# USB.net
KiCad netlist of a schematic drawn in Altium Designer
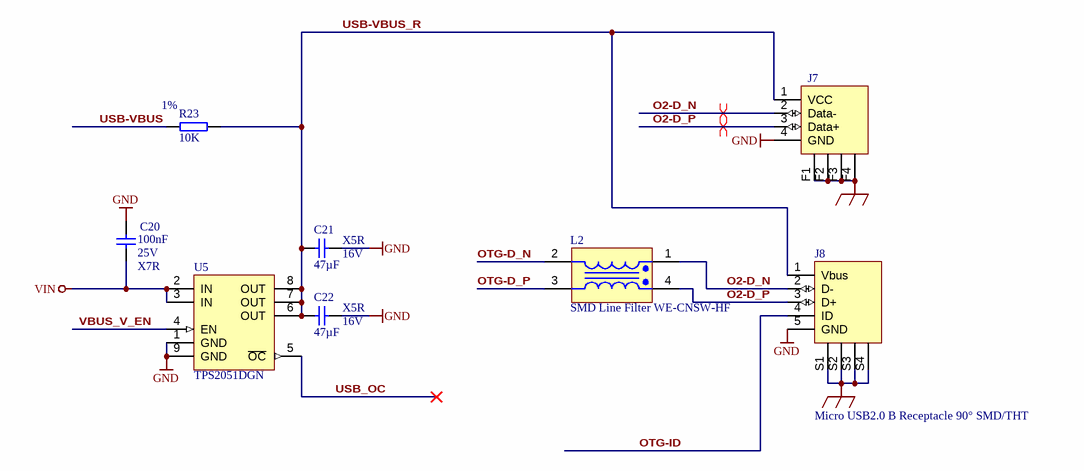
[diagram p0: USB.SchDoc]

(export (version "E")
  (design (tool "Eeschema 10.0.6"))
  (components
    (comp (ref "C20")
      (value "100nF")
      (footprint "CAPC1005X55N")
      (description "KON 100nF 25V X5R SMD")
      (fields (field (name "VOLTAGE") "25V") (field (name "TECHNOLOGY") "X7R"))
      (libsource (lib "TE") (part "CAP-NP"))
    )
    (comp (ref "C21")
      (value "47µF")
      (footprint "CAPC3216X180N")
      (description "KON 47µF 16V  X5R SMD 20%")
      (fields
        (field (name "VOLTAGE") "16V")
        (field (name "TECHNOLOGY") "X5R")
        (field (name "TOLERANCE") "20%")
      )
      (libsource (lib "TE") (part "CAP-NP"))
    )
    (comp (ref "C22")
      (value "47µF")
      (footprint "CAPC3216X180N")
      (description "KON 47µF 16V  X5R SMD 20%")
      (fields
        (field (name "VOLTAGE") "16V")
        (field (name "TECHNOLOGY") "X5R")
        (field (name "TOLERANCE") "20%")
      )
      (libsource (lib "TE") (part "CAP-NP"))
    )
    (comp (ref "J7")
      (value "USB A Buchse 90°")
      (footprint "73725-0110BLF")
      (libsource (lib "TE") (part "USB A 90"))
    )
    (comp (ref "J8")
      (value "Micro USB2.0 B Receptacle 90° SMD/THT")
      (footprint "629105150521")
      (fields (field (name "HELPURL") "‪B:\\AD\\adlib\\datasheet\\629105150521"))
      (libsource (lib "TE") (part "629105150521"))
    )
    (comp (ref "L2")
      (value "SMD Line Filter WE-CNSW-HF")
      (footprint "WE-CNSW-HF")
      (description "Stromkompensierter SMD Line Filter HF 320mA 0,24Ohm 50V")
      (fields (field (name "VOLTAGE") "320mA"))
      (libsource (lib "TE") (part "WE-CNSW-HF"))
    )
    (comp (ref "R23")
      (value "10K")
      (footprint "RESC1005X40N")
      (description "WID SMD 10K 1% 0,063W")
      (fields (field (name "TOLERANCE") "1%"))
      (libsource (lib "TE") (part "RES"))
    )
    (comp (ref "U5")
      (value "TPS2051DGN")
      (footprint "SOP65P488X107-9N-TI")
      (description "TPS2051BDGN")
      (libsource (lib "TE") (part "TPS2051DGN"))
    )
  )
  (nets
    (net (code "1") (name "/O2-D_N") (class "Default")
      (node (ref "J7") (pin "2") (pinfunction "Data-_2") (pintype "bidirectional"))
      (node (ref "J8") (pin "2") (pinfunction "D-_2") (pintype "bidirectional"))
      (node (ref "L2") (pin "1") (pintype "passive"))
    )
    (net (code "2") (name "/O2-D_P") (class "Default")
      (node (ref "J7") (pin "3") (pinfunction "Data+_3") (pintype "bidirectional"))
      (node (ref "J8") (pin "3") (pinfunction "D+_3") (pintype "bidirectional"))
      (node (ref "L2") (pin "4") (pintype "passive"))
    )
    (net (code "3") (name "/OTG-D_N") (class "Default") (node (ref "L2") (pin "2") (pintype "passive")))
    (net (code "4") (name "/OTG-D_P") (class "Default") (node (ref "L2") (pin "3") (pintype "passive")))
    (net (code "5") (name "/OTG-ID") (class "Default")
      (node (ref "J8") (pin "4") (pinfunction "ID_4") (pintype "passive"))
    )
    (net (code "6") (name "/USB-VBUS") (class "Default")
      (node (ref "R23") (pin "1") (pinfunction "1_1") (pintype "passive"))
    )
    (net (code "7") (name "/USB-VBUS_R") (class "Default")
      (node (ref "C21") (pin "1") (pinfunction "1_1") (pintype "passive"))
      (node (ref "C22") (pin "1") (pinfunction "1_1") (pintype "passive"))
      (node (ref "J7") (pin "1") (pinfunction "VCC_1") (pintype "power_in"))
      (node (ref "J8") (pin "1") (pinfunction "Vbus_1") (pintype "power_in"))
      (node (ref "R23") (pin "2") (pinfunction "2_2") (pintype "passive"))
      (node (ref "U5") (pin "6") (pinfunction "OUT_6") (pintype "power_in"))
      (node (ref "U5") (pin "7") (pinfunction "OUT_7") (pintype "power_in"))
      (node (ref "U5") (pin "8") (pinfunction "OUT_8") (pintype "power_in"))
    )
    (net (code "8") (name "/USB_OC") (class "Default")
      (node (ref "U5") (pin "5") (pinfunction "~{OC}_5") (pintype "output+no_connect"))
    )
    (net (code "9") (name "/VBUS_V_EN") (class "Default")
      (node (ref "U5") (pin "4") (pinfunction "EN_4") (pintype "input"))
    )
    (net (code "10") (name "FGND") (class "Default")
      (node (ref "J7") (pin "F1") (pinfunction "Frame_F1") (pintype "passive"))
      (node (ref "J7") (pin "F2") (pinfunction "Frame_F2") (pintype "passive"))
      (node (ref "J7") (pin "F3") (pinfunction "Frame_F3") (pintype "passive"))
      (node (ref "J7") (pin "F4") (pinfunction "Frame_F4") (pintype "passive"))
      (node (ref "J8") (pin "S1") (pinfunction "S1_S1") (pintype "passive"))
      (node (ref "J8") (pin "S2") (pinfunction "S2_S2") (pintype "passive"))
      (node (ref "J8") (pin "S3") (pinfunction "S3_S3") (pintype "passive"))
      (node (ref "J8") (pin "S4") (pinfunction "S4_S4") (pintype "passive"))
    )
    (net (code "11") (name "GND") (class "Default")
      (node (ref "C20") (pin "2") (pinfunction "2_2") (pintype "passive"))
      (node (ref "C21") (pin "2") (pinfunction "2_2") (pintype "passive"))
      (node (ref "C22") (pin "2") (pinfunction "2_2") (pintype "passive"))
      (node (ref "J7") (pin "4") (pinfunction "GND_4") (pintype "power_in"))
      (node (ref "J8") (pin "5") (pinfunction "GND_5") (pintype "power_in"))
      (node (ref "U5") (pin "1") (pinfunction "GND_1") (pintype "power_in"))
      (node (ref "U5") (pin "9") (pinfunction "GND_9") (pintype "power_in"))
    )
    (net (code "12") (name "VIN") (class "Default")
      (node (ref "C20") (pin "1") (pinfunction "1_1") (pintype "passive"))
      (node (ref "U5") (pin "2") (pinfunction "IN_2") (pintype "power_in"))
      (node (ref "U5") (pin "3") (pinfunction "IN_3") (pintype "power_in"))
    )
  )
)
